# pressure_esp_schematic.net
KiCad netlist of a schematic drawn in Altium Designer
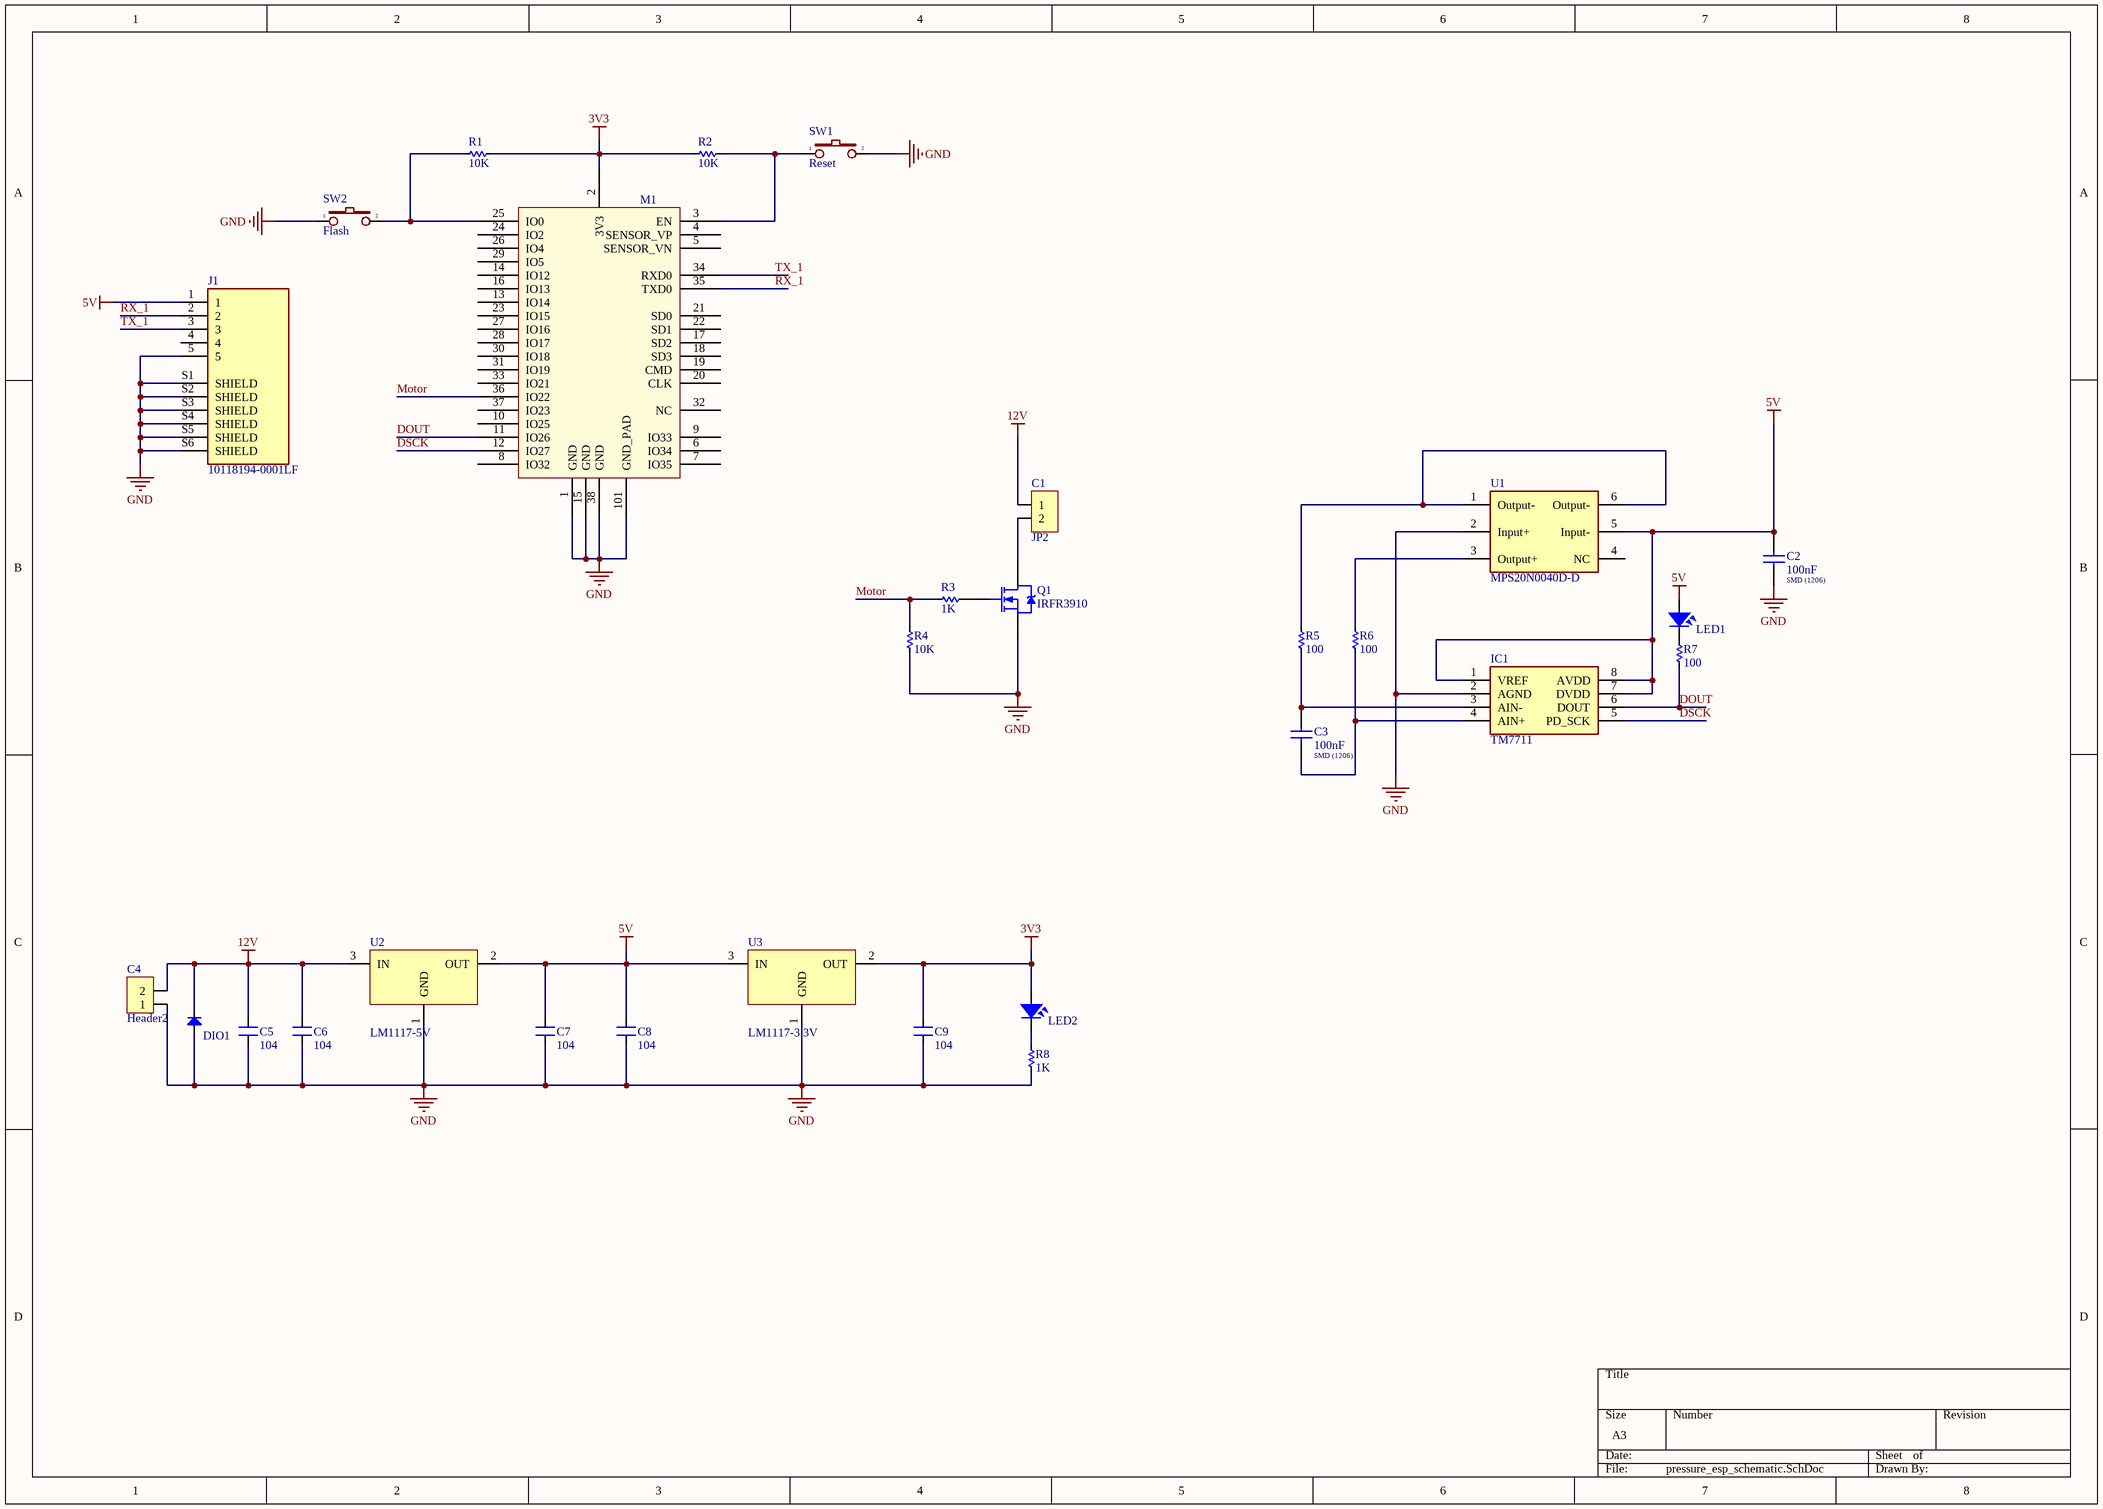
[diagram p0: pressure_esp_schematic.SchDoc]

(export (version "E")
  (design (tool "Eeschema 10.0.6"))
  (components
    (comp (ref "C1")
      (value "JP2")
      (footprint "JP2-D1T")
      (description "WR-PHD 2.54 mm Angled Socket Header")
      (fields
        (field (name "MANUFACTURER") "Würth Elektronik eiSos GmbH")
        (field (name "PARTNO") "613002143121")
        (field (name "CREATED BY") "Karrer Zheng")
      )
      (libsource (lib "LIBRARY") (part "JP2"))
    )
    (comp (ref "C2")
      (value "Capacitor SMD")
      (footprint "CAP_0603")
      (fields (field (name "VALOR") "100nF") (field (name "ENCAPSULAMENTO") "SMD (1206)"))
      (libsource (lib "Altium_Library_Brasil") (part "Capacitor SMD"))
    )
    (comp (ref "C3")
      (value "Capacitor SMD")
      (footprint "CAP_0603")
      (fields (field (name "VALOR") "100nF") (field (name "ENCAPSULAMENTO") "SMD (1206)"))
      (libsource (lib "Altium_Library_Brasil") (part "Capacitor SMD"))
    )
    (comp (ref "C4")
      (value "Header2")
      (footprint "Header2")
      (description "Header IDC, 2 x 1 Pin Vertical 2.54mm Pitch (Non-Boxed, Male)")
      (fields
        (field (name "MANUFACTURER") "Würth Elektronik eiSos GmbH")
        (field (name "PARTNO") "613002143121")
        (field (name "CREATED BY") "Karrer Zheng")
      )
      (libsource (lib "LIBRARY") (part "Header2"))
    )
    (comp (ref "C5")
      (value "104")
      (footprint "SM-CAP-0805")
      (fields (field (name "DESIGNED BY") "VanDungEvn"))
      (libsource (lib "electronicvn-library1") (part "CN"))
    )
    (comp (ref "C6")
      (value "104")
      (footprint "SM-CAP-0805")
      (fields (field (name "DESIGNED BY") "VanDungEvn"))
      (libsource (lib "electronicvn-library1") (part "CN"))
    )
    (comp (ref "C7")
      (value "104")
      (footprint "SM-CAP-0805")
      (fields (field (name "DESIGNED BY") "VanDungEvn"))
      (libsource (lib "electronicvn-library1") (part "CN"))
    )
    (comp (ref "C8")
      (value "104")
      (footprint "SM-CAP-0805")
      (fields (field (name "DESIGNED BY") "VanDungEvn"))
      (libsource (lib "electronicvn-library1") (part "CN"))
    )
    (comp (ref "C9")
      (value "104")
      (footprint "SM-CAP-0805")
      (fields (field (name "DESIGNED BY") "VanDungEvn"))
      (libsource (lib "electronicvn-library1") (part "CN"))
    )
    (comp (ref "DIO1")
      (value "Diode SMD")
      (footprint "DIO-SMD-106")
      (description "Default Diode")
      (fields (field (name "PUBLISHER") "Altium Limited"))
      (libsource (lib "LIBRARY") (part "Diode SMD"))
    )
    (comp (ref "IC1")
      (value "TM7711")
      (footprint "SamacSys:SOIC127P600X196-8N")
      (description "Integrated Circuit")
      (libsource (lib "*") (part "TM7711"))
    )
    (comp (ref "J1")
      (value "10118194-0001LF")
      (footprint "10118194-0001LF:AMPHENOL_10118194-0001LF")
      (description "USB - micro B USB 2.0 Receptacle Connector 5 Position Surface Mount, Right Angle; Through Hole")
      (fields (field (name "MF") "Amphenol ICC"))
      (libsource (lib "10118194-0001LF") (part "10118194-0001LF"))
    )
    (comp (ref "LED1") (value "LED") (footprint "LED-0805-Blue") (libsource (lib "LIBRARY") (part "LED SMD")))
    (comp (ref "LED2") (value "LED") (footprint "LED-0805-Blue") (libsource (lib "LIBRARY") (part "LED SMD")))
    (comp (ref "M1")
      (value "ESP32S_Module")
      (footprint "ESP32S")
      (description "Esp-32S")
      (libsource (lib "ESP32S") (part "ESP32S_Module"))
    )
    (comp (ref "Q1")
      (value "IRFR3910")
      (footprint "TO-252AA_N")
      (description "HEXFET Power MOSFET")
      (fields (field (name "PUBLISHER") "Altium Limited"))
      (libsource (lib "IR Discrete MOSFET - Power") (part "IRFR3910"))
    )
    (comp (ref "R1")
      (value "10K")
      (footprint "RES-SMD-0603")
      (description "Resistor")
      (fields
        (field (name "MANUFACTURER") "Generic Components")
        (field (name "PUBLISHER") "Altium Hobart Technology Centre")
      )
      (libsource (lib "LIBRARY") (part "Res-SMD"))
    )
    (comp (ref "R2")
      (value "10K")
      (footprint "RES-SMD-0603")
      (description "Resistor")
      (fields
        (field (name "MANUFACTURER") "Generic Components")
        (field (name "PUBLISHER") "Altium Hobart Technology Centre")
      )
      (libsource (lib "LIBRARY") (part "Res-SMD"))
    )
    (comp (ref "R3")
      (value "1K")
      (footprint "RES-SMD-0603")
      (description "Resistor")
      (fields
        (field (name "MANUFACTURER") "Generic Components")
        (field (name "PUBLISHER") "Altium Hobart Technology Centre")
      )
      (libsource (lib "LIBRARY") (part "Res-SMD"))
    )
    (comp (ref "R4")
      (value "10K")
      (footprint "RES-SMD-0603")
      (description "Resistor")
      (fields
        (field (name "MANUFACTURER") "Generic Components")
        (field (name "PUBLISHER") "Altium Hobart Technology Centre")
      )
      (libsource (lib "LIBRARY") (part "Res-SMD"))
    )
    (comp (ref "R5")
      (value "100")
      (footprint "RES-SMD-0603")
      (description "Resistor")
      (fields
        (field (name "MANUFACTURER") "Generic Components")
        (field (name "PUBLISHER") "Altium Hobart Technology Centre")
      )
      (libsource (lib "LIBRARY") (part "Res-SMD"))
    )
    (comp (ref "R6")
      (value "100")
      (footprint "RES-SMD-0603")
      (description "Resistor")
      (fields
        (field (name "MANUFACTURER") "Generic Components")
        (field (name "PUBLISHER") "Altium Hobart Technology Centre")
      )
      (libsource (lib "LIBRARY") (part "Res-SMD"))
    )
    (comp (ref "R7")
      (value "100")
      (footprint "RES-SMD-0603")
      (description "Resistor")
      (fields
        (field (name "MANUFACTURER") "Generic Components")
        (field (name "PUBLISHER") "Altium Hobart Technology Centre")
      )
      (libsource (lib "LIBRARY") (part "Res-SMD"))
    )
    (comp (ref "R8")
      (value "1K")
      (footprint "RES-SMD-0603")
      (description "Resistor")
      (fields
        (field (name "MANUFACTURER") "Generic Components")
        (field (name "PUBLISHER") "Altium Hobart Technology Centre")
      )
      (libsource (lib "LIBRARY") (part "Res-SMD"))
    )
    (comp (ref "SW1")
      (value "Reset")
      (footprint "SW1-SMD")
      (description "Switch button 2 pin")
      (libsource (lib "LIBRARY") (part "SW2"))
    )
    (comp (ref "SW2")
      (value "Flash")
      (footprint "SW-DIP1-1")
      (description "Switch button 2 pin")
      (libsource (lib "LIBRARY") (part "SW2"))
    )
    (comp (ref "U1")
      (value "MPS20N0040D-D")
      (footprint "MPS20N0040D-D:XDCR_ADP5241")
      (description "Pressure Sensor 14.5PSI (100kPa) Vented Gauge Male - 0.12 (3mm) Tube 0 V ~ 4.5 V 6-SMD Module")
      (fields (field (name "MP") "ADP5241") (field (name "MF") "Panasonic"))
      (libsource (lib "MPS20N0040D-D") (part "MPS20N0040D-D"))
    )
    (comp (ref "U2")
      (value "LM1117-5V")
      (footprint "SOT223")
      (description "800mA Low-Dropout Linear Regulator")
      (fields (field (name "CREATOR") "Nguyen Ba Bien"))
      (libsource (lib "LIBRARY") (part "LM1117"))
    )
    (comp (ref "U3")
      (value "LM1117-3.3V")
      (footprint "SOT223")
      (description "800mA Low-Dropout Linear Regulator")
      (fields (field (name "CREATOR") "Nguyen Ba Bien"))
      (libsource (lib "LIBRARY") (part "LM1117"))
    )
  )
  (nets
    (net (code "1") (name "/DOUT") (class "Default")
      (node (ref "IC1") (pin "6") (pinfunction "DOUT_6") (pintype "passive"))
      (node (ref "M1") (pin "11") (pinfunction "IO26_11") (pintype "passive"))
      (node (ref "R7") (pin "2") (pinfunction "2_2") (pintype "passive"))
    )
    (net (code "2") (name "/DSCK") (class "Default")
      (node (ref "IC1") (pin "5") (pinfunction "PD_SCK_5") (pintype "passive"))
      (node (ref "M1") (pin "12") (pinfunction "IO27_12") (pintype "passive"))
    )
    (net (code "3") (name "/Motor") (class "Default")
      (node (ref "M1") (pin "36") (pinfunction "IO22_36") (pintype "passive"))
      (node (ref "R3") (pin "1") (pinfunction "1_1") (pintype "passive"))
      (node (ref "R4") (pin "1") (pinfunction "1_1") (pintype "passive"))
    )
    (net (code "4") (name "/RX_1") (class "Default")
      (node (ref "J1") (pin "2") (pinfunction "2_2") (pintype "passive"))
      (node (ref "M1") (pin "35") (pinfunction "TXD0_35") (pintype "passive"))
    )
    (net (code "5") (name "/TX_1") (class "Default")
      (node (ref "J1") (pin "3") (pinfunction "3_3") (pintype "passive"))
      (node (ref "M1") (pin "34") (pinfunction "RXD0_34") (pintype "passive"))
    )
    (net (code "6") (name "3V3") (class "Default")
      (node (ref "C9") (pin "2") (pinfunction "2_2") (pintype "passive"))
      (node (ref "LED2") (pin "1") (pinfunction "1_1") (pintype "passive"))
      (node (ref "M1") (pin "2") (pinfunction "3V3_2") (pintype "power_in"))
      (node (ref "R1") (pin "1") (pinfunction "1_1") (pintype "passive"))
      (node (ref "R2") (pin "2") (pinfunction "2_2") (pintype "passive"))
      (node (ref "U3") (pin "2") (pinfunction "OUT_2") (pintype "passive"))
    )
    (net (code "7") (name "5V") (class "Default")
      (node (ref "C2") (pin "2") (pinfunction "2_2") (pintype "passive"))
      (node (ref "C7") (pin "2") (pinfunction "2_2") (pintype "passive"))
      (node (ref "C8") (pin "2") (pinfunction "2_2") (pintype "passive"))
      (node (ref "IC1") (pin "1") (pinfunction "VREF_1") (pintype "passive"))
      (node (ref "IC1") (pin "7") (pinfunction "DVDD_7") (pintype "passive"))
      (node (ref "IC1") (pin "8") (pinfunction "AVDD_8") (pintype "passive"))
      (node (ref "J1") (pin "1") (pinfunction "1_1") (pintype "passive"))
      (node (ref "LED1") (pin "1") (pinfunction "1_1") (pintype "passive"))
      (node (ref "U1") (pin "5") (pinfunction "Input-_5") (pintype "power_in"))
      (node (ref "U2") (pin "2") (pinfunction "OUT_2") (pintype "passive"))
      (node (ref "U3") (pin "3") (pinfunction "IN_3") (pintype "passive"))
    )
    (net (code "8") (name "12V") (class "Default")
      (node (ref "C1") (pin "1") (pinfunction "1_1") (pintype "passive"))
      (node (ref "C4") (pin "2") (pinfunction "2_2") (pintype "passive"))
      (node (ref "C5") (pin "2") (pinfunction "2_2") (pintype "passive"))
      (node (ref "C6") (pin "2") (pinfunction "2_2") (pintype "passive"))
      (node (ref "DIO1") (pin "2") (pinfunction "K_2") (pintype "passive"))
      (node (ref "U2") (pin "3") (pinfunction "IN_3") (pintype "passive"))
    )
    (net (code "9") (name "GND") (class "Default")
      (node (ref "C2") (pin "1") (pinfunction "1_1") (pintype "passive"))
      (node (ref "C4") (pin "1") (pinfunction "1_1") (pintype "passive"))
      (node (ref "C5") (pin "1") (pinfunction "1_1") (pintype "passive"))
      (node (ref "C6") (pin "1") (pinfunction "1_1") (pintype "passive"))
      (node (ref "C7") (pin "1") (pinfunction "1_1") (pintype "passive"))
      (node (ref "C8") (pin "1") (pinfunction "1_1") (pintype "passive"))
      (node (ref "C9") (pin "1") (pinfunction "1_1") (pintype "passive"))
      (node (ref "DIO1") (pin "1") (pinfunction "A_1") (pintype "passive"))
      (node (ref "IC1") (pin "2") (pinfunction "AGND_2") (pintype "passive"))
      (node (ref "J1") (pin "5") (pinfunction "5_5") (pintype "passive"))
      (node (ref "J1") (pin "S1") (pinfunction "SHIELD_S1") (pintype "passive"))
      (node (ref "J1") (pin "S2") (pinfunction "SHIELD_S2") (pintype "passive"))
      (node (ref "J1") (pin "S3") (pinfunction "SHIELD_S3") (pintype "passive"))
      (node (ref "J1") (pin "S4") (pinfunction "SHIELD_S4") (pintype "passive"))
      (node (ref "J1") (pin "S5") (pinfunction "SHIELD_S5") (pintype "passive"))
      (node (ref "J1") (pin "S6") (pinfunction "SHIELD_S6") (pintype "passive"))
      (node (ref "M1") (pin "1") (pinfunction "GND_1") (pintype "power_in"))
      (node (ref "M1") (pin "101") (pinfunction "GND_PAD_101") (pintype "power_in"))
      (node (ref "M1") (pin "15") (pinfunction "GND_15") (pintype "power_in"))
      (node (ref "M1") (pin "38") (pinfunction "GND_38") (pintype "power_in"))
      (node (ref "Q1") (pin "3") (pinfunction "S_3") (pintype "passive"))
      (node (ref "R4") (pin "2") (pinfunction "2_2") (pintype "passive"))
      (node (ref "R8") (pin "2") (pinfunction "2_2") (pintype "passive"))
      (node (ref "SW1") (pin "2") (pinfunction "2_2") (pintype "passive"))
      (node (ref "SW2") (pin "1") (pinfunction "1_1") (pintype "passive"))
      (node (ref "U1") (pin "2") (pinfunction "Input+_2") (pintype "power_in"))
      (node (ref "U2") (pin "1") (pinfunction "GND_1") (pintype "passive"))
      (node (ref "U3") (pin "1") (pinfunction "GND_1") (pintype "passive"))
    )
    (net (code "10") (name "Net-(IC1-AIN+)") (class "Default")
      (node (ref "C3") (pin "1") (pinfunction "1_1") (pintype "passive"))
      (node (ref "IC1") (pin "4") (pinfunction "AIN+_4") (pintype "passive"))
      (node (ref "R6") (pin "2") (pinfunction "2_2") (pintype "passive"))
    )
    (net (code "11") (name "Net-(IC1-AIN-)") (class "Default")
      (node (ref "C3") (pin "2") (pinfunction "2_2") (pintype "passive"))
      (node (ref "IC1") (pin "3") (pinfunction "AIN-_3") (pintype "passive"))
      (node (ref "R5") (pin "2") (pinfunction "2_2") (pintype "passive"))
    )
    (net (code "12") (name "Net-(LED1-Pad2)") (class "Default")
      (node (ref "LED1") (pin "2") (pinfunction "2_2") (pintype "passive"))
      (node (ref "R7") (pin "1") (pinfunction "1_1") (pintype "passive"))
    )
    (net (code "13") (name "Net-(LED2-Pad2)") (class "Default")
      (node (ref "LED2") (pin "2") (pinfunction "2_2") (pintype "passive"))
      (node (ref "R8") (pin "1") (pinfunction "1_1") (pintype "passive"))
    )
    (net (code "14") (name "Net-(M1-EN)") (class "Default")
      (node (ref "M1") (pin "3") (pinfunction "EN_3") (pintype "power_in"))
      (node (ref "R2") (pin "1") (pinfunction "1_1") (pintype "passive"))
      (node (ref "SW1") (pin "1") (pinfunction "1_1") (pintype "passive"))
    )
    (net (code "15") (name "Net-(M1-IO0)") (class "Default")
      (node (ref "M1") (pin "25") (pinfunction "IO0_25") (pintype "passive"))
      (node (ref "R1") (pin "2") (pinfunction "2_2") (pintype "passive"))
      (node (ref "SW2") (pin "2") (pinfunction "2_2") (pintype "passive"))
    )
    (net (code "16") (name "Net-(Q1-D)") (class "Default")
      (node (ref "C1") (pin "2") (pinfunction "2_2") (pintype "passive"))
      (node (ref "Q1") (pin "4") (pinfunction "D_4") (pintype "passive"))
    )
    (net (code "17") (name "Net-(Q1-G)") (class "Default")
      (node (ref "Q1") (pin "1") (pinfunction "G_1") (pintype "passive"))
      (node (ref "R3") (pin "2") (pinfunction "2_2") (pintype "passive"))
    )
    (net (code "18") (name "Net-(R5-Pad1)") (class "Default")
      (node (ref "R5") (pin "1") (pinfunction "1_1") (pintype "passive"))
      (node (ref "U1") (pin "1") (pinfunction "Output-_1") (pintype "power_in"))
      (node (ref "U1") (pin "6") (pinfunction "Output-_6") (pintype "power_in"))
    )
    (net (code "19") (name "Net-(U1-Output+)") (class "Default")
      (node (ref "R6") (pin "1") (pinfunction "1_1") (pintype "passive"))
      (node (ref "U1") (pin "3") (pinfunction "Output+_3") (pintype "power_in"))
    )
    (net (code "20") (name "unconnected-(J1-Pad4)") (class "Default")
      (node (ref "J1") (pin "4") (pinfunction "4_4") (pintype "passive"))
    )
    (net (code "21") (name "unconnected-(M1-CLK-Pad20)") (class "Default")
      (node (ref "M1") (pin "20") (pinfunction "CLK_20") (pintype "passive"))
    )
    (net (code "22") (name "unconnected-(M1-CMD-Pad19)") (class "Default")
      (node (ref "M1") (pin "19") (pinfunction "CMD_19") (pintype "passive"))
    )
    (net (code "23") (name "unconnected-(M1-IO2-Pad24)") (class "Default")
      (node (ref "M1") (pin "24") (pinfunction "IO2_24") (pintype "passive"))
    )
    (net (code "24") (name "unconnected-(M1-IO4-Pad26)") (class "Default")
      (node (ref "M1") (pin "26") (pinfunction "IO4_26") (pintype "passive"))
    )
    (net (code "25") (name "unconnected-(M1-IO5-Pad29)") (class "Default")
      (node (ref "M1") (pin "29") (pinfunction "IO5_29") (pintype "passive"))
    )
    (net (code "26") (name "unconnected-(M1-IO12-Pad14)") (class "Default")
      (node (ref "M1") (pin "14") (pinfunction "IO12_14") (pintype "passive"))
    )
    (net (code "27") (name "unconnected-(M1-IO13-Pad16)") (class "Default")
      (node (ref "M1") (pin "16") (pinfunction "IO13_16") (pintype "passive"))
    )
    (net (code "28") (name "unconnected-(M1-IO14-Pad13)") (class "Default")
      (node (ref "M1") (pin "13") (pinfunction "IO14_13") (pintype "passive"))
    )
    (net (code "29") (name "unconnected-(M1-IO15-Pad23)") (class "Default")
      (node (ref "M1") (pin "23") (pinfunction "IO15_23") (pintype "passive"))
    )
    (net (code "30") (name "unconnected-(M1-IO16-Pad27)") (class "Default")
      (node (ref "M1") (pin "27") (pinfunction "IO16_27") (pintype "passive"))
    )
    (net (code "31") (name "unconnected-(M1-IO17-Pad28)") (class "Default")
      (node (ref "M1") (pin "28") (pinfunction "IO17_28") (pintype "passive"))
    )
    (net (code "32") (name "unconnected-(M1-IO18-Pad30)") (class "Default")
      (node (ref "M1") (pin "30") (pinfunction "IO18_30") (pintype "passive"))
    )
    (net (code "33") (name "unconnected-(M1-IO19-Pad31)") (class "Default")
      (node (ref "M1") (pin "31") (pinfunction "IO19_31") (pintype "passive"))
    )
    (net (code "34") (name "unconnected-(M1-IO21-Pad33)") (class "Default")
      (node (ref "M1") (pin "33") (pinfunction "IO21_33") (pintype "passive"))
    )
    (net (code "35") (name "unconnected-(M1-IO23-Pad37)") (class "Default")
      (node (ref "M1") (pin "37") (pinfunction "IO23_37") (pintype "passive"))
    )
    (net (code "36") (name "unconnected-(M1-IO25-Pad10)") (class "Default")
      (node (ref "M1") (pin "10") (pinfunction "IO25_10") (pintype "passive"))
    )
    (net (code "37") (name "unconnected-(M1-IO32-Pad8)") (class "Default")
      (node (ref "M1") (pin "8") (pinfunction "IO32_8") (pintype "passive"))
    )
    (net (code "38") (name "unconnected-(M1-IO33-Pad9)") (class "Default")
      (node (ref "M1") (pin "9") (pinfunction "IO33_9") (pintype "passive"))
    )
    (net (code "39") (name "unconnected-(M1-IO34-Pad6)") (class "Default")
      (node (ref "M1") (pin "6") (pinfunction "IO34_6") (pintype "passive"))
    )
    (net (code "40") (name "unconnected-(M1-IO35-Pad7)") (class "Default")
      (node (ref "M1") (pin "7") (pinfunction "IO35_7") (pintype "passive"))
    )
    (net (code "41") (name "unconnected-(M1-NC-Pad32)") (class "Default")
      (node (ref "M1") (pin "32") (pinfunction "NC_32") (pintype "passive"))
    )
    (net (code "42") (name "unconnected-(M1-SD0-Pad21)") (class "Default")
      (node (ref "M1") (pin "21") (pinfunction "SD0_21") (pintype "passive"))
    )
    (net (code "43") (name "unconnected-(M1-SD1-Pad22)") (class "Default")
      (node (ref "M1") (pin "22") (pinfunction "SD1_22") (pintype "passive"))
    )
    (net (code "44") (name "unconnected-(M1-SD2-Pad17)") (class "Default")
      (node (ref "M1") (pin "17") (pinfunction "SD2_17") (pintype "passive"))
    )
    (net (code "45") (name "unconnected-(M1-SD3-Pad18)") (class "Default")
      (node (ref "M1") (pin "18") (pinfunction "SD3_18") (pintype "passive"))
    )
    (net (code "46") (name "unconnected-(M1-SENSOR_VN-Pad5)") (class "Default")
      (node (ref "M1") (pin "5") (pinfunction "SENSOR_VN_5") (pintype "passive"))
    )
    (net (code "47") (name "unconnected-(M1-SENSOR_VP-Pad4)") (class "Default")
      (node (ref "M1") (pin "4") (pinfunction "SENSOR_VP_4") (pintype "passive"))
    )
    (net (code "48") (name "unconnected-(U1-NC-Pad4)") (class "Default")
      (node (ref "U1") (pin "4") (pinfunction "NC_4") (pintype "power_in"))
    )
  )
)
